# Sheet2.net
KiCad netlist of a schematic drawn in Altium Designer
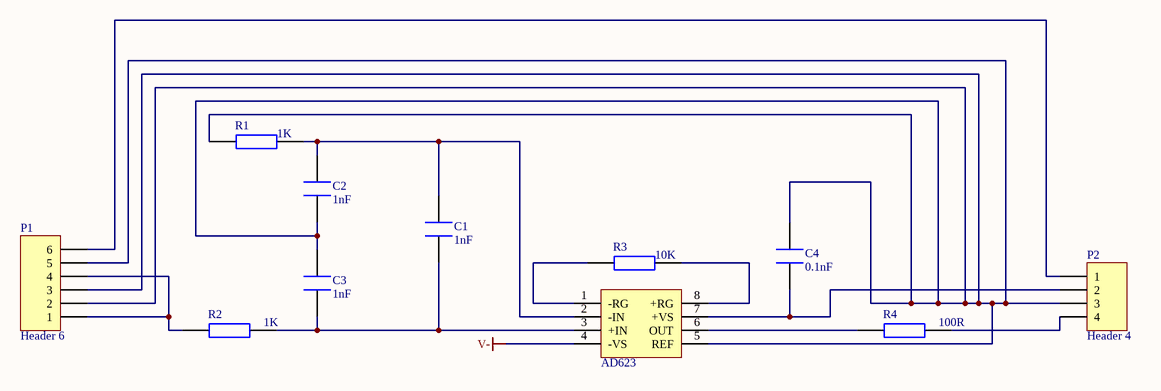
[diagram p0: Sheet2.SchDoc]

(export (version "E")
  (design (tool "Eeschema 10.0.6"))
  (components
    (comp (ref "C1")
      (value "1nF")
      (footprint "0402")
      (description "电容")
      (libsource (lib "Schlib1") (part "CAP"))
    )
    (comp (ref "C2")
      (value "1nF")
      (footprint "0402")
      (description "电容")
      (libsource (lib "Schlib1") (part "CAP"))
    )
    (comp (ref "C3")
      (value "1nF")
      (footprint "0402")
      (description "电容")
      (libsource (lib "Schlib1") (part "CAP"))
    )
    (comp (ref "C4")
      (value "0.1nF")
      (footprint "0402")
      (description "电容")
      (libsource (lib "Schlib1") (part "CAP"))
    )
    (comp (ref "IC1")
      (value "AD623")
      (footprint "SO8_M")
      (description "IC")
      (libsource (lib "Schlib1") (part "AD623"))
    )
    (comp (ref "P1")
      (value "Header 6")
      (footprint "软排线6p")
      (description "Header, 6-Pin")
      (fields (field (name "PUBLISHER") "Altium Limited"))
      (libsource (lib "Miscellaneous Connectors") (part "Header 6"))
    )
    (comp (ref "P2")
      (value "Header 4")
      (footprint "软排线4p")
      (description "Header, 4-Pin")
      (fields (field (name "PUBLISHER") "Altium Limited"))
      (libsource (lib "Miscellaneous Connectors") (part "Header 4"))
    )
    (comp (ref "R1")
      (value "1K")
      (footprint "0402-A")
      (description "电阻")
      (libsource (lib "Schlib1") (part "RES"))
    )
    (comp (ref "R2")
      (value "1K")
      (footprint "0402-A")
      (description "电阻")
      (libsource (lib "Schlib1") (part "RES"))
    )
    (comp (ref "R3")
      (value "10K")
      (footprint "0402-A")
      (description "电阻")
      (libsource (lib "Schlib1") (part "RES"))
    )
    (comp (ref "R4")
      (value "100R")
      (footprint "0402-A")
      (description "电阻")
      (libsource (lib "Schlib1") (part "RES"))
    )
  )
  (nets
    (net (code "2") (name "Net-(IC1-+IN)") (class "Default")
      (node (ref "C1") (pin "1") (pinfunction "1_1") (pintype "passive"))
      (node (ref "C3") (pin "1") (pinfunction "1_1") (pintype "passive"))
      (node (ref "IC1") (pin "3") (pinfunction "+IN_3") (pintype "passive"))
      (node (ref "R2") (pin "2") (pinfunction "2_2") (pintype "passive"))
    )
    (net (code "3") (name "Net-(IC1-+RG)") (class "Default")
      (node (ref "IC1") (pin "8") (pinfunction "+RG_8") (pintype "passive"))
      (node (ref "R3") (pin "2") (pinfunction "2_2") (pintype "passive"))
    )
    (net (code "4") (name "Net-(IC1-+VS)") (class "Default")
      (node (ref "C4") (pin "1") (pinfunction "1_1") (pintype "passive"))
      (node (ref "IC1") (pin "7") (pinfunction "+VS_7") (pintype "passive"))
      (node (ref "P2") (pin "2") (pinfunction "2_2") (pintype "passive"))
    )
    (net (code "5") (name "Net-(IC1--IN)") (class "Default")
      (node (ref "C1") (pin "2") (pinfunction "2_2") (pintype "passive"))
      (node (ref "C2") (pin "2") (pinfunction "2_2") (pintype "passive"))
      (node (ref "IC1") (pin "2") (pinfunction "-IN_2") (pintype "passive"))
      (node (ref "R1") (pin "2") (pinfunction "2_2") (pintype "passive"))
    )
    (net (code "6") (name "Net-(IC1--RG)") (class "Default")
      (node (ref "IC1") (pin "1") (pinfunction "-RG_1") (pintype "passive"))
      (node (ref "R3") (pin "1") (pinfunction "1_1") (pintype "passive"))
    )
    (net (code "7") (name "Net-(IC1-OUT)") (class "Default")
      (node (ref "IC1") (pin "6") (pinfunction "OUT_6") (pintype "passive"))
      (node (ref "R4") (pin "1") (pinfunction "1_1") (pintype "passive"))
    )
    (net (code "8") (name "Net-(IC1-REF)") (class "Default")
      (node (ref "C2") (pin "1") (pinfunction "1_1") (pintype "passive"))
      (node (ref "C3") (pin "2") (pinfunction "2_2") (pintype "passive"))
      (node (ref "C4") (pin "2") (pinfunction "2_2") (pintype "passive"))
      (node (ref "IC1") (pin "5") (pinfunction "REF_5") (pintype "passive"))
      (node (ref "P1") (pin "2") (pinfunction "2_2") (pintype "passive"))
      (node (ref "P1") (pin "3") (pinfunction "3_3") (pintype "passive"))
      (node (ref "P1") (pin "5") (pinfunction "5_5") (pintype "passive"))
      (node (ref "P2") (pin "3") (pinfunction "3_3") (pintype "passive"))
      (node (ref "R1") (pin "1") (pinfunction "1_1") (pintype "passive"))
    )
    (net (code "9") (name "Net-(P1-Pad1)") (class "Default")
      (node (ref "P1") (pin "1") (pinfunction "1_1") (pintype "passive"))
      (node (ref "P1") (pin "4") (pinfunction "4_4") (pintype "passive"))
      (node (ref "R2") (pin "1") (pinfunction "1_1") (pintype "passive"))
    )
    (net (code "10") (name "Net-(P1-Pad6)") (class "Default")
      (node (ref "P1") (pin "6") (pinfunction "6_6") (pintype "passive"))
      (node (ref "P2") (pin "1") (pinfunction "1_1") (pintype "passive"))
    )
    (net (code "11") (name "Net-(P2-Pad4)") (class "Default")
      (node (ref "P2") (pin "4") (pinfunction "4_4") (pintype "passive"))
      (node (ref "R4") (pin "2") (pinfunction "2_2") (pintype "passive"))
    )
    (net (code "12") (name "V-") (class "Default")
      (node (ref "IC1") (pin "4") (pinfunction "-VS_4") (pintype "passive"))
    )
  )
)
